# SCH_Flaps__2023-07-31.net
KiCad netlist of a schematic drawn in EasyEDA
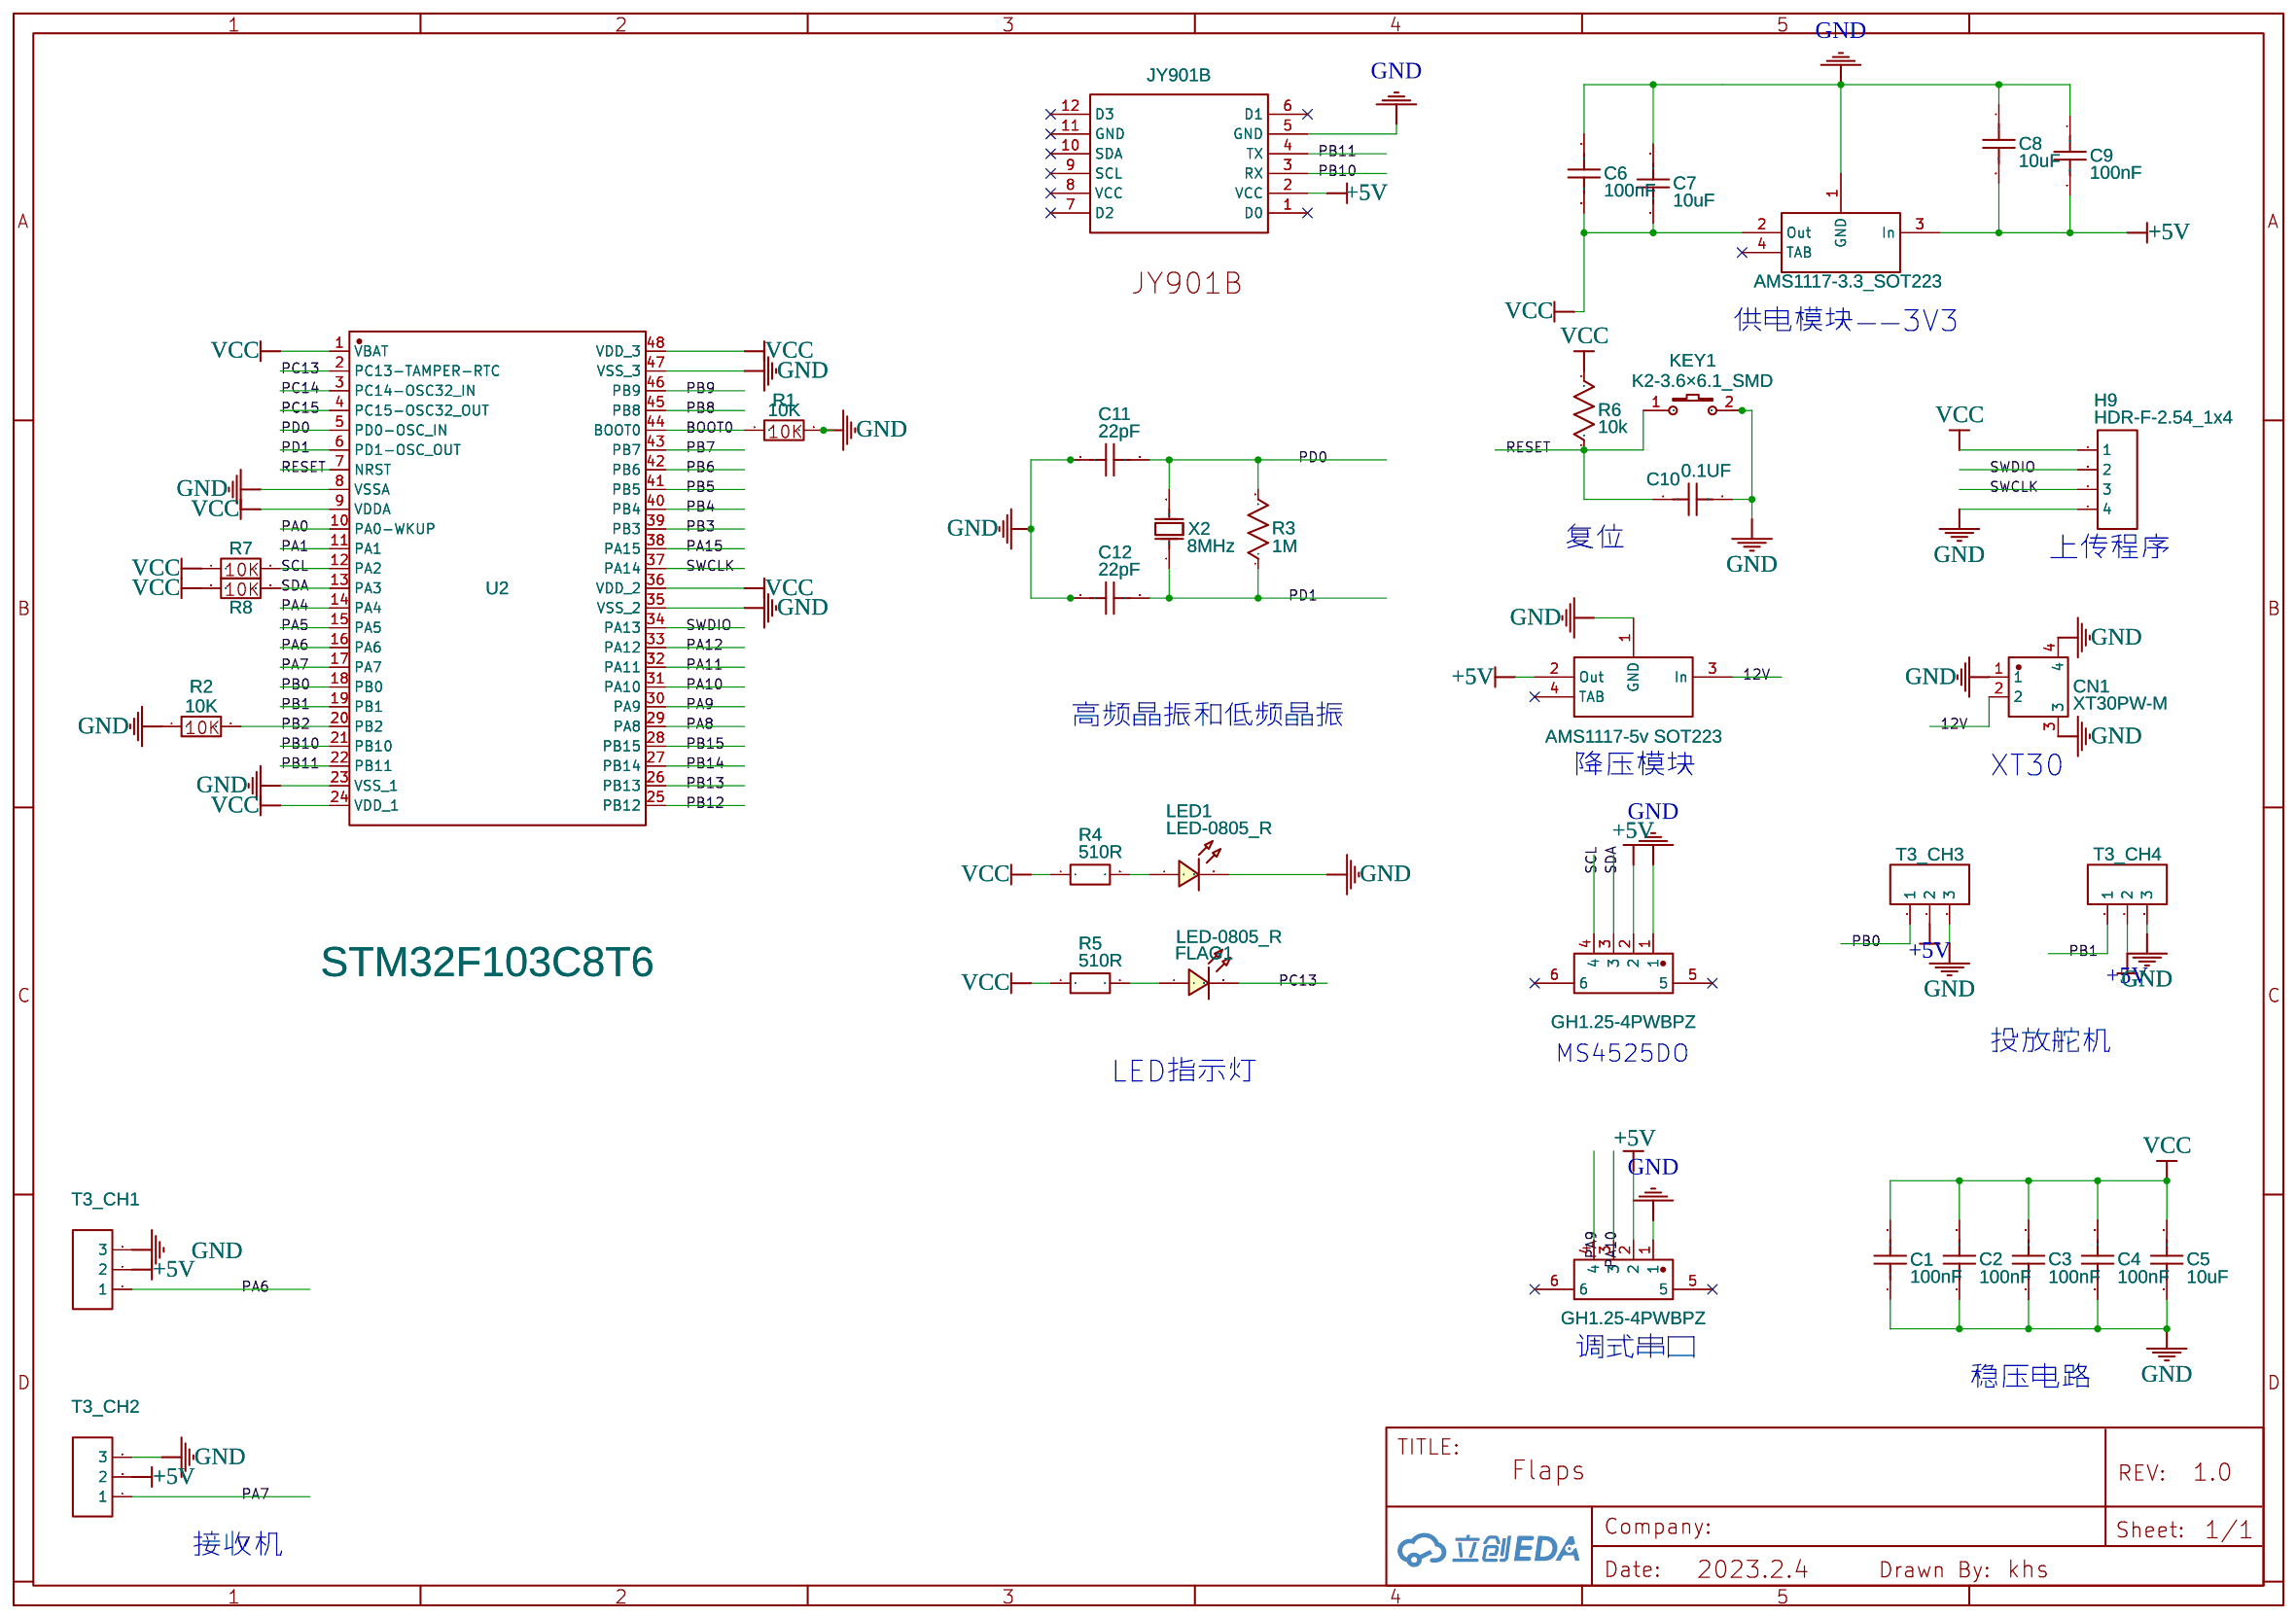
[diagram p0: schematic sheet]

(export (version "E")
  (design (tool "Eeschema 10.0.6"))
  (components
    (comp (ref "C1") (value "100nF") (libsource (lib "") (part "C_0603_US_1")))
    (comp (ref "C2") (value "100nF") (libsource (lib "") (part "C_0603_US_1")))
    (comp (ref "C3") (value "100nF") (libsource (lib "") (part "C_0603_US_1")))
    (comp (ref "C4") (value "100nF") (libsource (lib "") (part "C_0603_US_1")))
    (comp (ref "C5") (value "10uF") (libsource (lib "") (part "C_0603_US_1")))
    (comp (ref "C6")
      (value "100nF")
      (fields (field (name "Manufacturer Part") "CL10B104KC8NNNC") (field (name "Manufacturer") "SAMSUNG"))
      (libsource (lib "") (part "CL10B104KC8NNNC"))
    )
    (comp (ref "C7")
      (value "10uF")
      (fields
        (field (name "Manufacturer Part") "EMK316AB7106KL-T")
        (field (name "Manufacturer") "Taiyo Yuden")
      )
      (libsource (lib "") (part "EMK316AB7106KL-T"))
    )
    (comp (ref "C8")
      (value "10uF")
      (fields
        (field (name "Manufacturer Part") "EMK316AB7106KL-T")
        (field (name "Manufacturer") "Taiyo Yuden")
      )
      (libsource (lib "") (part "EMK316AB7106KL-T"))
    )
    (comp (ref "C9")
      (value "100nF")
      (fields (field (name "Manufacturer Part") "CL10B104KC8NNNC") (field (name "Manufacturer") "SAMSUNG"))
      (libsource (lib "") (part "CL10B104KC8NNNC"))
    )
    (comp (ref "C10") (value "0.1UF") (libsource (lib "") (part "C_0603_US")))
    (comp (ref "C11") (value "22pF") (libsource (lib "") (part "C_0603_US")))
    (comp (ref "C12") (value "22pF") (libsource (lib "") (part "C_0603_US")))
    (comp (ref "CN1")
      (value "XT30PW-M")
      (fields (field (name "Manufacturer") "Changzhou Amass Elec"))
      (libsource (lib "") (part "XT30PW-M"))
    )
    (comp (ref "FLAG1")
      (value "LED-0805_R")
      (fields
        (field (name "Manufacturer Part") "17-21SURC/S530-A3/TR8")
        (field (name "Manufacturer") "EVERLIGHT(台湾亿光)")
      )
      (libsource (lib "") (part "LED-0805_R"))
    )
    (comp (ref "H9") (value "HDR-F-2.54_1x4") (libsource (lib "") (part "HDR-F-2.54_1x4")))
    (comp (ref "KEY1")
      (value "K2-3.6×6.1_SMD")
      (fields (field (name "Manufacturer Part") "K2-1107ST-A4SW-06"))
      (libsource (lib "") (part "K2-3.6×6.1_SMD"))
    )
    (comp (ref "LED1")
      (value "LED-0805_R")
      (fields
        (field (name "Manufacturer Part") "17-21SURC/S530-A3/TR8")
        (field (name "Manufacturer") "EVERLIGHT(台湾亿光)")
      )
      (libsource (lib "") (part "LED-0805_R_1"))
    )
    (comp (ref "R1") (value "10K") (libsource (lib "") (part "10K电阻R0603_1")))
    (comp (ref "R2") (value "10K") (libsource (lib "") (part "10K电阻R0603")))
    (comp (ref "R3") (value "1M") (libsource (lib "") (part "R_0603_US")))
    (comp (ref "R4") (value "510R") (libsource (lib "") (part "R_0603_EU")))
    (comp (ref "R5") (value "510R") (libsource (lib "") (part "R_0603_EU")))
    (comp (ref "R6") (value "10k") (libsource (lib "") (part "R_0603_US")))
    (comp (ref "R7") (value "10K") (libsource (lib "") (part "10K电阻R0603")))
    (comp (ref "R8") (value "10K") (libsource (lib "") (part "10K电阻R0603")))
    (comp (ref "T3_CH1") (value "HDR-F-2.54_1x3") (libsource (lib "") (part "HDR-F-2.54_1x3")))
    (comp (ref "T3_CH2") (value "HDR-F-2.54_1x3") (libsource (lib "") (part "HDR-F-2.54_1x3")))
    (comp (ref "T3_CH3") (value "HDR-F-2.54_1x3") (libsource (lib "") (part "HDR-F-2.54_1x3_1")))
    (comp (ref "T3_CH4") (value "HDR-F-2.54_1x3") (libsource (lib "") (part "HDR-F-2.54_1x3_1")))
    (comp (ref "U1")
      (value "AMS1117-3.3_SOT223")
      (fields (field (name "Manufacturer Part") "AMS1117-3.3") (field (name "Manufacturer") "SK"))
      (libsource (lib "") (part "AMS1117-3.3_C165482"))
    )
    (comp (ref "U2")
      (value "STM32F103C8T6")
      (fields (field (name "Manufacturer") "STMicroelectronics"))
      (libsource (lib "") (part "STM32F103C8T6"))
    )
    (comp (ref "U3")
      (value "AMS1117-5v SOT223")
      (fields (field (name "Manufacturer Part") "AMS1117-3.3") (field (name "Manufacturer") "SK"))
      (libsource (lib "") (part "AMS1117-3.3_C165482"))
    )
    (comp (ref "U4")
      (value "GH1.25-4PWBPZ")
      (fields (field (name "Manufacturer") "BOOMELE(博穆精密)"))
      (libsource (lib "") (part "GH1.25-4PWBPZ"))
    )
    (comp (ref "U5")
      (value "GH1.25-4PWBPZ")
      (fields (field (name "Manufacturer") "BOOMELE(博穆精密)"))
      (libsource (lib "") (part "GH1.25-4PWBPZ"))
    )
    (comp (ref "U9") (value "JY901B") (libsource (lib "") (part "JY901B")))
    (comp (ref "X2")
      (value "8MHz")
      (fields (field (name "Manufacturer Part") "ESB8.00000F20E22") (field (name "Manufacturer") "HOSONIC"))
      (libsource (lib "") (part "ESB8.00000F20E22"))
    )
  )
  (nets
    (net (code "1") (name "+5V") (class "Default")
      (node (ref "C8") (pin "2") (pinfunction "2_2") (pintype "unspecified"))
      (node (ref "C9") (pin "2") (pinfunction "2_2") (pintype "unspecified"))
      (node (ref "T3_CH1") (pin "2") (pinfunction "2_2") (pintype "input"))
      (node (ref "T3_CH2") (pin "2") (pinfunction "2_2") (pintype "input"))
      (node (ref "T3_CH3") (pin "2") (pinfunction "2_2") (pintype "input"))
      (node (ref "T3_CH4") (pin "2") (pinfunction "2_2") (pintype "input"))
      (node (ref "U1") (pin "3") (pinfunction "In_3") (pintype "unspecified"))
      (node (ref "U3") (pin "2") (pinfunction "Out_2") (pintype "unspecified"))
      (node (ref "U4") (pin "2") (pinfunction "2_2") (pintype "unspecified"))
      (node (ref "U5") (pin "2") (pinfunction "2_2") (pintype "unspecified"))
      (node (ref "U9") (pin "2") (pinfunction "VCC_2") (pintype "unspecified"))
    )
    (net (code "2") (name "/12V") (class "Default")
      (node (ref "CN1") (pin "2") (pinfunction "2_2") (pintype "unspecified"))
      (node (ref "U3") (pin "3") (pinfunction "In_3") (pintype "unspecified"))
    )
    (net (code "3") (name "/BOOT0") (class "Default")
      (node (ref "R1") (pin "1") (pinfunction "1_1") (pintype "unspecified"))
      (node (ref "U2") (pin "44") (pinfunction "BOOT0_44") (pintype "unspecified"))
    )
    (net (code "4") (name "/PA0") (class "Default")
      (node (ref "U2") (pin "10") (pinfunction "PA0-WKUP_10") (pintype "unspecified"))
    )
    (net (code "5") (name "/PA1") (class "Default")
      (node (ref "U2") (pin "11") (pinfunction "PA1_11") (pintype "unspecified"))
    )
    (net (code "6") (name "/PA4") (class "Default")
      (node (ref "U2") (pin "14") (pinfunction "PA4_14") (pintype "unspecified"))
    )
    (net (code "7") (name "/PA5") (class "Default")
      (node (ref "U2") (pin "15") (pinfunction "PA5_15") (pintype "unspecified"))
    )
    (net (code "8") (name "/PA6") (class "Default")
      (node (ref "T3_CH1") (pin "1") (pinfunction "1_1") (pintype "input"))
      (node (ref "U2") (pin "16") (pinfunction "PA6_16") (pintype "unspecified"))
    )
    (net (code "9") (name "/PA7") (class "Default")
      (node (ref "T3_CH2") (pin "1") (pinfunction "1_1") (pintype "input"))
      (node (ref "U2") (pin "17") (pinfunction "PA7_17") (pintype "unspecified"))
    )
    (net (code "10") (name "/PA8") (class "Default")
      (node (ref "U2") (pin "29") (pinfunction "PA8_29") (pintype "unspecified"))
    )
    (net (code "11") (name "/PA9") (class "Default")
      (node (ref "U2") (pin "30") (pinfunction "PA9_30") (pintype "unspecified"))
      (node (ref "U5") (pin "4") (pinfunction "4_4") (pintype "unspecified"))
    )
    (net (code "12") (name "/PA10") (class "Default")
      (node (ref "U2") (pin "31") (pinfunction "PA10_31") (pintype "unspecified"))
      (node (ref "U5") (pin "3") (pinfunction "3_3") (pintype "unspecified"))
    )
    (net (code "13") (name "/PA11") (class "Default")
      (node (ref "U2") (pin "32") (pinfunction "PA11_32") (pintype "unspecified"))
    )
    (net (code "14") (name "/PA12") (class "Default")
      (node (ref "U2") (pin "33") (pinfunction "PA12_33") (pintype "unspecified"))
    )
    (net (code "15") (name "/PA15") (class "Default")
      (node (ref "U2") (pin "38") (pinfunction "PA15_38") (pintype "unspecified"))
    )
    (net (code "16") (name "/PB0") (class "Default")
      (node (ref "T3_CH3") (pin "1") (pinfunction "1_1") (pintype "input"))
      (node (ref "U2") (pin "18") (pinfunction "PB0_18") (pintype "unspecified"))
    )
    (net (code "17") (name "/PB1") (class "Default")
      (node (ref "T3_CH4") (pin "1") (pinfunction "1_1") (pintype "input"))
      (node (ref "U2") (pin "19") (pinfunction "PB1_19") (pintype "unspecified"))
    )
    (net (code "18") (name "/PB2") (class "Default")
      (node (ref "R2") (pin "2") (pinfunction "2_2") (pintype "unspecified"))
      (node (ref "U2") (pin "20") (pinfunction "PB2_20") (pintype "unspecified"))
    )
    (net (code "19") (name "/PB3") (class "Default")
      (node (ref "U2") (pin "39") (pinfunction "PB3_39") (pintype "unspecified"))
    )
    (net (code "20") (name "/PB4") (class "Default")
      (node (ref "U2") (pin "40") (pinfunction "PB4_40") (pintype "unspecified"))
    )
    (net (code "21") (name "/PB5") (class "Default")
      (node (ref "U2") (pin "41") (pinfunction "PB5_41") (pintype "unspecified"))
    )
    (net (code "22") (name "/PB6") (class "Default")
      (node (ref "U2") (pin "42") (pinfunction "PB6_42") (pintype "unspecified"))
    )
    (net (code "23") (name "/PB7") (class "Default")
      (node (ref "U2") (pin "43") (pinfunction "PB7_43") (pintype "unspecified"))
    )
    (net (code "24") (name "/PB8") (class "Default")
      (node (ref "U2") (pin "45") (pinfunction "PB8_45") (pintype "unspecified"))
    )
    (net (code "25") (name "/PB9") (class "Default")
      (node (ref "U2") (pin "46") (pinfunction "PB9_46") (pintype "unspecified"))
    )
    (net (code "26") (name "/PB10") (class "Default")
      (node (ref "U2") (pin "21") (pinfunction "PB10_21") (pintype "unspecified"))
      (node (ref "U9") (pin "3") (pinfunction "RX_3") (pintype "unspecified"))
    )
    (net (code "27") (name "/PB11") (class "Default")
      (node (ref "U2") (pin "22") (pinfunction "PB11_22") (pintype "unspecified"))
      (node (ref "U9") (pin "4") (pinfunction "TX_4") (pintype "unspecified"))
    )
    (net (code "28") (name "/PB12") (class "Default")
      (node (ref "U2") (pin "25") (pinfunction "PB12_25") (pintype "unspecified"))
    )
    (net (code "29") (name "/PB13") (class "Default")
      (node (ref "U2") (pin "26") (pinfunction "PB13_26") (pintype "unspecified"))
    )
    (net (code "30") (name "/PB14") (class "Default")
      (node (ref "U2") (pin "27") (pinfunction "PB14_27") (pintype "unspecified"))
    )
    (net (code "31") (name "/PB15") (class "Default")
      (node (ref "U2") (pin "28") (pinfunction "PB15_28") (pintype "unspecified"))
    )
    (net (code "32") (name "/PC13") (class "Default")
      (node (ref "FLAG1") (pin "2") (pinfunction "2_2") (pintype "unspecified"))
      (node (ref "U2") (pin "2") (pinfunction "PC13-TAMPER-RTC_2") (pintype "unspecified"))
    )
    (net (code "33") (name "/PC14") (class "Default")
      (node (ref "U2") (pin "3") (pinfunction "PC14-OSC32_IN_3") (pintype "unspecified"))
    )
    (net (code "34") (name "/PC15") (class "Default")
      (node (ref "U2") (pin "4") (pinfunction "PC15-OSC32_OUT_4") (pintype "unspecified"))
    )
    (net (code "35") (name "/PD0") (class "Default")
      (node (ref "C11") (pin "2") (pinfunction "2_2") (pintype "unspecified"))
      (node (ref "R3") (pin "2") (pinfunction "2_2") (pintype "unspecified"))
      (node (ref "U2") (pin "5") (pinfunction "PD0-OSC_IN_5") (pintype "unspecified"))
      (node (ref "X2") (pin "2") (pinfunction "OSC2_2") (pintype "input"))
    )
    (net (code "36") (name "/PD1") (class "Default")
      (node (ref "C12") (pin "2") (pinfunction "2_2") (pintype "unspecified"))
      (node (ref "R3") (pin "1") (pinfunction "1_1") (pintype "unspecified"))
      (node (ref "U2") (pin "6") (pinfunction "PD1-OSC_OUT_6") (pintype "unspecified"))
      (node (ref "X2") (pin "1") (pinfunction "OSC1_1") (pintype "input"))
    )
    (net (code "37") (name "/RESET") (class "Default")
      (node (ref "C10") (pin "1") (pinfunction "1_1") (pintype "unspecified"))
      (node (ref "KEY1") (pin "1") (pinfunction "1_1") (pintype "unspecified"))
      (node (ref "R6") (pin "1") (pinfunction "1_1") (pintype "unspecified"))
      (node (ref "U2") (pin "7") (pinfunction "NRST_7") (pintype "unspecified"))
    )
    (net (code "38") (name "/SCL") (class "Default")
      (node (ref "R7") (pin "2") (pinfunction "2_2") (pintype "unspecified"))
      (node (ref "U2") (pin "12") (pinfunction "PA2_12") (pintype "unspecified"))
      (node (ref "U4") (pin "4") (pinfunction "4_4") (pintype "unspecified"))
    )
    (net (code "39") (name "/SDA") (class "Default")
      (node (ref "R8") (pin "2") (pinfunction "2_2") (pintype "unspecified"))
      (node (ref "U2") (pin "13") (pinfunction "PA3_13") (pintype "unspecified"))
      (node (ref "U4") (pin "3") (pinfunction "3_3") (pintype "unspecified"))
    )
    (net (code "40") (name "/SWCLK") (class "Default")
      (node (ref "H9") (pin "3") (pinfunction "3_3") (pintype "unspecified"))
      (node (ref "U2") (pin "37") (pinfunction "PA14_37") (pintype "unspecified"))
    )
    (net (code "41") (name "/SWDIO") (class "Default")
      (node (ref "H9") (pin "2") (pinfunction "2_2") (pintype "unspecified"))
      (node (ref "U2") (pin "34") (pinfunction "PA13_34") (pintype "unspecified"))
    )
    (net (code "42") (name "GND") (class "Default")
      (node (ref "C1") (pin "1") (pinfunction "1_1") (pintype "unspecified"))
      (node (ref "C10") (pin "2") (pinfunction "2_2") (pintype "unspecified"))
      (node (ref "C11") (pin "1") (pinfunction "1_1") (pintype "unspecified"))
      (node (ref "C12") (pin "1") (pinfunction "1_1") (pintype "unspecified"))
      (node (ref "C2") (pin "1") (pinfunction "1_1") (pintype "unspecified"))
      (node (ref "C3") (pin "1") (pinfunction "1_1") (pintype "unspecified"))
      (node (ref "C4") (pin "1") (pinfunction "1_1") (pintype "unspecified"))
      (node (ref "C5") (pin "1") (pinfunction "1_1") (pintype "unspecified"))
      (node (ref "C6") (pin "1") (pinfunction "1_1") (pintype "unspecified"))
      (node (ref "C7") (pin "1") (pinfunction "1_1") (pintype "unspecified"))
      (node (ref "C8") (pin "1") (pinfunction "1_1") (pintype "unspecified"))
      (node (ref "C9") (pin "1") (pinfunction "1_1") (pintype "unspecified"))
      (node (ref "CN1") (pin "1") (pinfunction "1_1") (pintype "unspecified"))
      (node (ref "CN1") (pin "3") (pinfunction "3_3") (pintype "unspecified"))
      (node (ref "CN1") (pin "4") (pinfunction "4_4") (pintype "unspecified"))
      (node (ref "H9") (pin "4") (pinfunction "4_4") (pintype "unspecified"))
      (node (ref "KEY1") (pin "2") (pinfunction "2_2") (pintype "unspecified"))
      (node (ref "LED1") (pin "2") (pinfunction "2_2") (pintype "unspecified"))
      (node (ref "R1") (pin "2") (pinfunction "2_2") (pintype "unspecified"))
      (node (ref "R2") (pin "1") (pinfunction "1_1") (pintype "unspecified"))
      (node (ref "T3_CH1") (pin "3") (pinfunction "3_3") (pintype "input"))
      (node (ref "T3_CH2") (pin "3") (pinfunction "3_3") (pintype "input"))
      (node (ref "T3_CH3") (pin "3") (pinfunction "3_3") (pintype "input"))
      (node (ref "T3_CH4") (pin "3") (pinfunction "3_3") (pintype "input"))
      (node (ref "U1") (pin "1") (pinfunction "GND_1") (pintype "unspecified"))
      (node (ref "U2") (pin "23") (pinfunction "VSS_1_23") (pintype "unspecified"))
      (node (ref "U2") (pin "35") (pinfunction "VSS_2_35") (pintype "unspecified"))
      (node (ref "U2") (pin "47") (pinfunction "VSS_3_47") (pintype "unspecified"))
      (node (ref "U2") (pin "8") (pinfunction "VSSA_8") (pintype "unspecified"))
      (node (ref "U3") (pin "1") (pinfunction "GND_1") (pintype "unspecified"))
      (node (ref "U4") (pin "1") (pinfunction "1_1") (pintype "unspecified"))
      (node (ref "U5") (pin "1") (pinfunction "1_1") (pintype "unspecified"))
      (node (ref "U9") (pin "5") (pinfunction "GND_5") (pintype "unspecified"))
    )
    (net (code "43") (name "Net-(FLAG1-Pad1)") (class "Default")
      (node (ref "FLAG1") (pin "1") (pinfunction "1_1") (pintype "unspecified"))
      (node (ref "R5") (pin "2") (pinfunction "2_2") (pintype "unspecified"))
    )
    (net (code "44") (name "Net-(LED1-Pad1)") (class "Default")
      (node (ref "LED1") (pin "1") (pinfunction "1_1") (pintype "unspecified"))
      (node (ref "R4") (pin "2") (pinfunction "2_2") (pintype "unspecified"))
    )
    (net (code "45") (name "VCC") (class "Default")
      (node (ref "C1") (pin "2") (pinfunction "2_2") (pintype "unspecified"))
      (node (ref "C2") (pin "2") (pinfunction "2_2") (pintype "unspecified"))
      (node (ref "C3") (pin "2") (pinfunction "2_2") (pintype "unspecified"))
      (node (ref "C4") (pin "2") (pinfunction "2_2") (pintype "unspecified"))
      (node (ref "C5") (pin "2") (pinfunction "2_2") (pintype "unspecified"))
      (node (ref "C6") (pin "2") (pinfunction "2_2") (pintype "unspecified"))
      (node (ref "C7") (pin "2") (pinfunction "2_2") (pintype "unspecified"))
      (node (ref "H9") (pin "1") (pinfunction "1_1") (pintype "unspecified"))
      (node (ref "R4") (pin "1") (pinfunction "1_1") (pintype "unspecified"))
      (node (ref "R5") (pin "1") (pinfunction "1_1") (pintype "unspecified"))
      (node (ref "R6") (pin "2") (pinfunction "2_2") (pintype "unspecified"))
      (node (ref "R7") (pin "1") (pinfunction "1_1") (pintype "unspecified"))
      (node (ref "R8") (pin "1") (pinfunction "1_1") (pintype "unspecified"))
      (node (ref "U1") (pin "2") (pinfunction "Out_2") (pintype "unspecified"))
      (node (ref "U2") (pin "1") (pinfunction "VBAT_1") (pintype "unspecified"))
      (node (ref "U2") (pin "24") (pinfunction "VDD_1_24") (pintype "unspecified"))
      (node (ref "U2") (pin "36") (pinfunction "VDD_2_36") (pintype "unspecified"))
      (node (ref "U2") (pin "48") (pinfunction "VDD_3_48") (pintype "unspecified"))
      (node (ref "U2") (pin "9") (pinfunction "VDDA_9") (pintype "unspecified"))
    )
    (net (code "46") (name "unconnected-(U1-TAB-Pad4)") (class "Default")
      (node (ref "U1") (pin "4") (pinfunction "TAB_4") (pintype "unspecified+no_connect"))
    )
    (net (code "47") (name "unconnected-(U3-TAB-Pad4)") (class "Default")
      (node (ref "U3") (pin "4") (pinfunction "TAB_4") (pintype "unspecified+no_connect"))
    )
    (net (code "48") (name "unconnected-(U4-Pad5)") (class "Default")
      (node (ref "U4") (pin "5") (pinfunction "5_5") (pintype "unspecified+no_connect"))
    )
    (net (code "49") (name "unconnected-(U4-Pad6)") (class "Default")
      (node (ref "U4") (pin "6") (pinfunction "6_6") (pintype "unspecified+no_connect"))
    )
    (net (code "50") (name "unconnected-(U5-Pad5)") (class "Default")
      (node (ref "U5") (pin "5") (pinfunction "5_5") (pintype "unspecified+no_connect"))
    )
    (net (code "51") (name "unconnected-(U5-Pad6)") (class "Default")
      (node (ref "U5") (pin "6") (pinfunction "6_6") (pintype "unspecified+no_connect"))
    )
    (net (code "52") (name "unconnected-(U9-D0-Pad1)") (class "Default")
      (node (ref "U9") (pin "1") (pinfunction "D0_1") (pintype "unspecified+no_connect"))
    )
    (net (code "53") (name "unconnected-(U9-D1-Pad6)") (class "Default")
      (node (ref "U9") (pin "6") (pinfunction "D1_6") (pintype "unspecified+no_connect"))
    )
    (net (code "54") (name "unconnected-(U9-D2-Pad7)") (class "Default")
      (node (ref "U9") (pin "7") (pinfunction "D2_7") (pintype "unspecified+no_connect"))
    )
    (net (code "55") (name "unconnected-(U9-D3-Pad12)") (class "Default")
      (node (ref "U9") (pin "12") (pinfunction "D3_12") (pintype "unspecified+no_connect"))
    )
    (net (code "56") (name "unconnected-(U9-GND-Pad11)") (class "Default")
      (node (ref "U9") (pin "11") (pinfunction "GND_11") (pintype "unspecified+no_connect"))
    )
    (net (code "57") (name "unconnected-(U9-SCL-Pad9)") (class "Default")
      (node (ref "U9") (pin "9") (pinfunction "SCL_9") (pintype "unspecified+no_connect"))
    )
    (net (code "58") (name "unconnected-(U9-SDA-Pad10)") (class "Default")
      (node (ref "U9") (pin "10") (pinfunction "SDA_10") (pintype "unspecified+no_connect"))
    )
    (net (code "59") (name "unconnected-(U9-VCC-Pad8)") (class "Default")
      (node (ref "U9") (pin "8") (pinfunction "VCC_8") (pintype "unspecified+no_connect"))
    )
  )
)
